# ESP32_with_USBC_SCH.net
KiCad netlist of a schematic drawn in Altium Designer
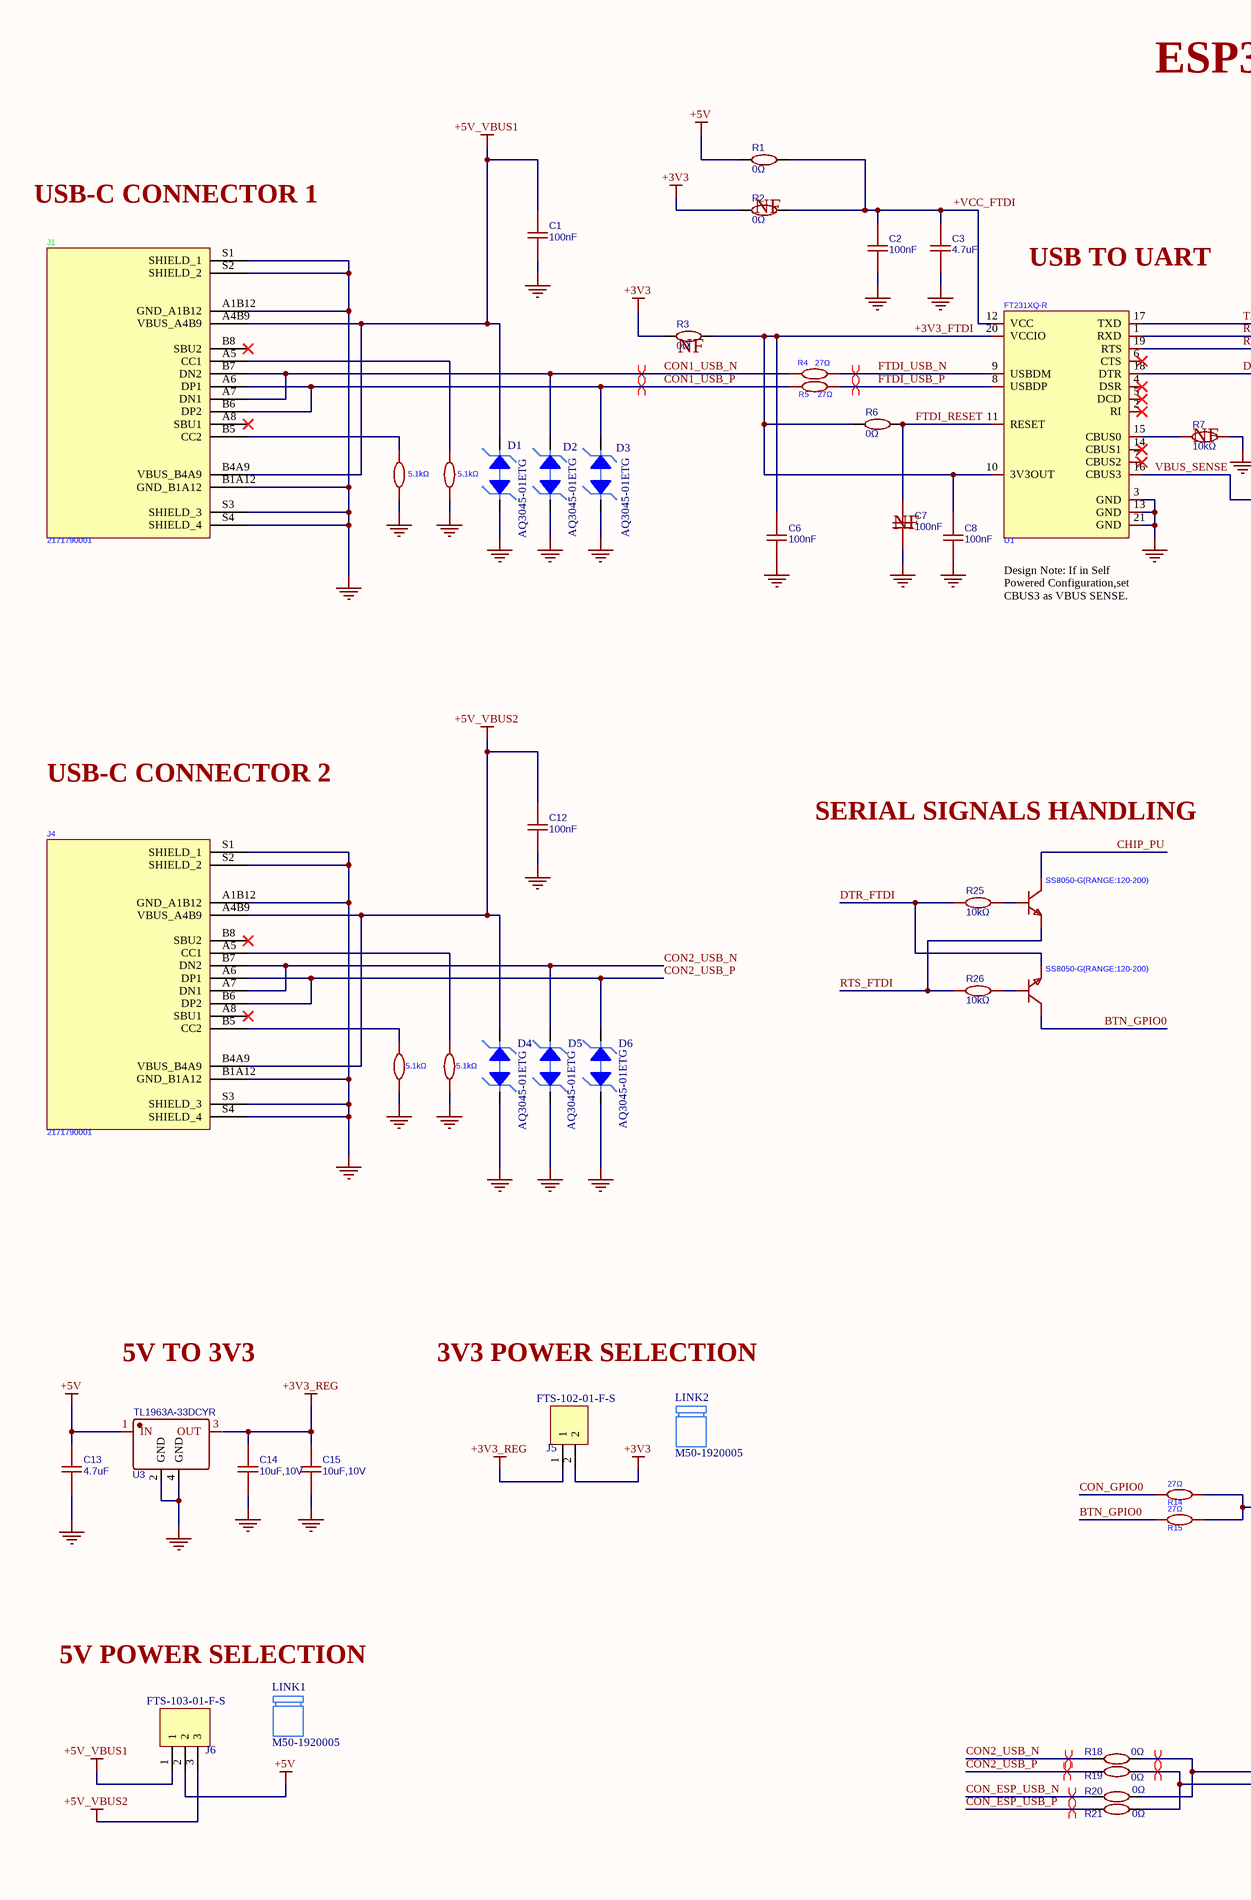
[diagram p0: ESP32 with USBC SCH.SchDoc, left]
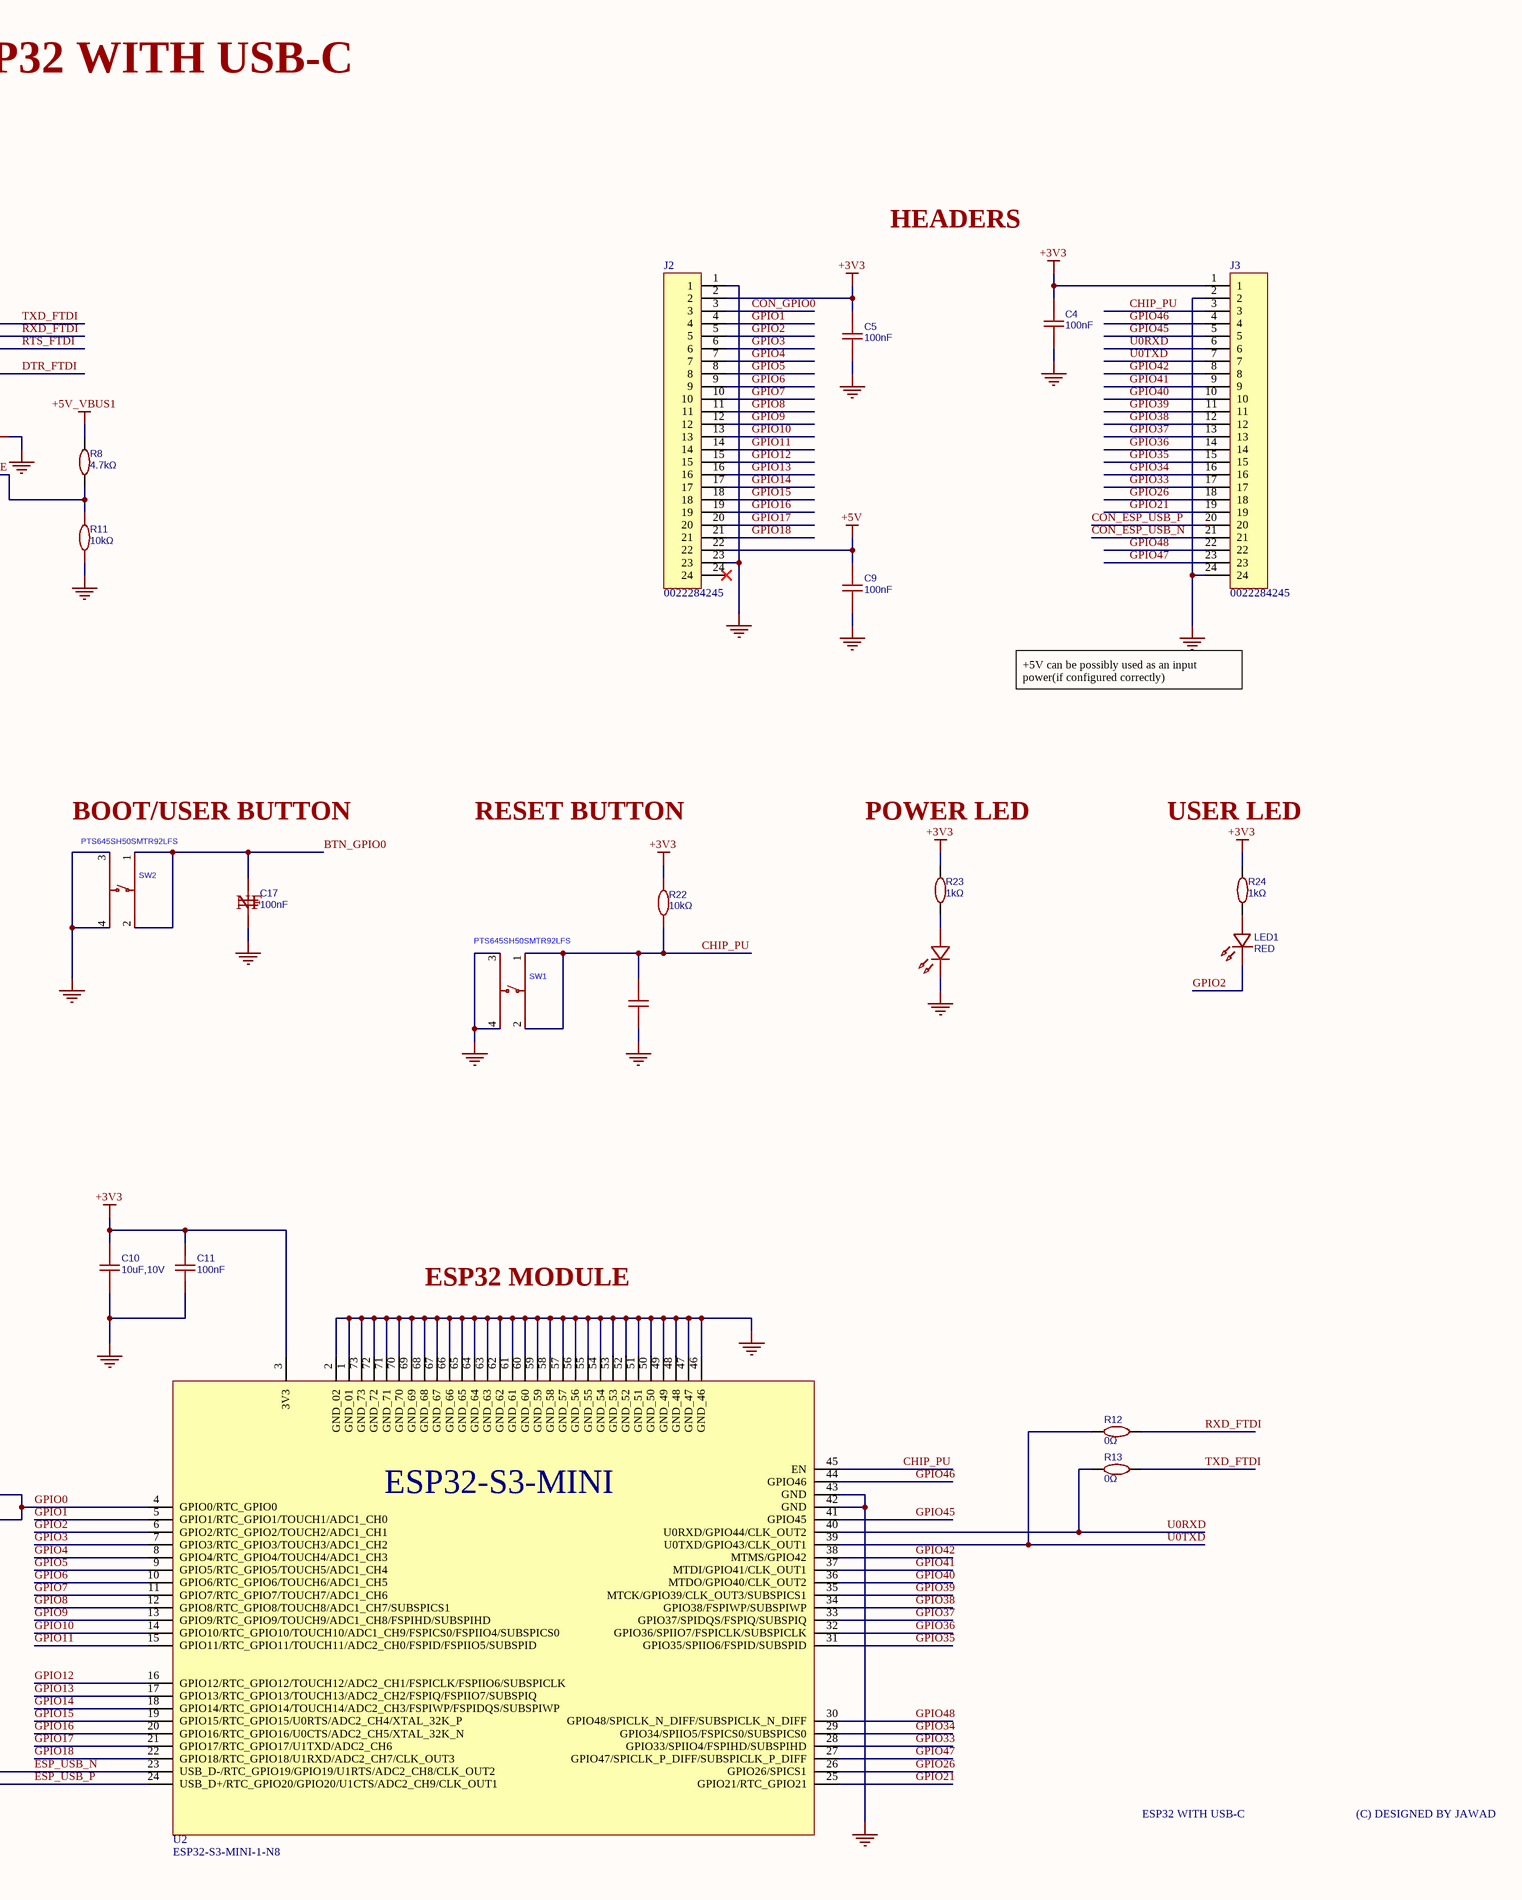
[diagram p1: ESP32 with USBC SCH.SchDoc, right]

(export (version "E")
  (design (tool "Eeschema 10.0.6"))
  (components
    (comp (ref "C1")
      (value "100nF")
      (footprint "C0402")
      (description "CAP CER 0.1UF 50V X7R 0402")
      (fields
        (field (name "MANUFACTURER") "SAMSUNG(三星)")
        (field (name "MANUFACTURER PART") "CL05B104KB5NNNC")
        (field (name "CONTRIBUTOR") "LCSC")
      )
      (libsource (lib "Schlib") (part "100nF,50V"))
    )
    (comp (ref "C2")
      (value "100nF")
      (footprint "C0402")
      (description "CAP CER 0.1UF 50V X7R 0402")
      (fields
        (field (name "MANUFACTURER") "SAMSUNG(三星)")
        (field (name "MANUFACTURER PART") "CL05B104KB5NNNC")
        (field (name "CONTRIBUTOR") "LCSC")
      )
      (libsource (lib "Schlib") (part "100nF,50V"))
    )
    (comp (ref "C3")
      (value "4.7uF")
      (footprint "C0402")
      (description "CAP CER 4.7UF 16V X5R 0402")
      (fields
        (field (name "MANUFACTURER") "SAMSUNG(三星)")
        (field (name "MANUFACTURER PART") "CL05A475MO5NUNC")
        (field (name "CONTRIBUTOR") "LCSC")
      )
      (libsource (lib "Schlib") (part "4.7uF"))
    )
    (comp (ref "C4")
      (value "100nF")
      (footprint "C0402")
      (description "CAP CER 0.1UF 50V X7R 0402")
      (fields
        (field (name "MANUFACTURER") "SAMSUNG(三星)")
        (field (name "MANUFACTURER PART") "CL05B104KB5NNNC")
        (field (name "CONTRIBUTOR") "LCSC")
      )
      (libsource (lib "Schlib") (part "100nF,50V"))
    )
    (comp (ref "C5")
      (value "100nF")
      (footprint "C0402")
      (description "CAP CER 0.1UF 50V X7R 0402")
      (fields
        (field (name "MANUFACTURER") "SAMSUNG(三星)")
        (field (name "MANUFACTURER PART") "CL05B104KB5NNNC")
        (field (name "CONTRIBUTOR") "LCSC")
      )
      (libsource (lib "Schlib") (part "100nF,50V"))
    )
    (comp (ref "C6")
      (value "100nF")
      (footprint "C0402")
      (description "CAP CER 0.1UF 50V X7R 0402")
      (fields
        (field (name "MANUFACTURER") "SAMSUNG(三星)")
        (field (name "MANUFACTURER PART") "CL05B104KB5NNNC")
        (field (name "CONTRIBUTOR") "LCSC")
      )
      (libsource (lib "Schlib") (part "100nF,50V"))
    )
    (comp (ref "C7")
      (value "100nF")
      (footprint "C0402")
      (description "CAP CER 0.1UF 50V X7R 0402")
      (fields
        (field (name "MANUFACTURER") "SAMSUNG(三星)")
        (field (name "MANUFACTURER PART") "CL05B104KB5NNNC")
        (field (name "CONTRIBUTOR") "LCSC")
      )
      (libsource (lib "Schlib") (part "100nF,50V"))
    )
    (comp (ref "C8")
      (value "100nF")
      (footprint "C0402")
      (description "CAP CER 0.1UF 50V X7R 0402")
      (fields
        (field (name "MANUFACTURER") "SAMSUNG(三星)")
        (field (name "MANUFACTURER PART") "CL05B104KB5NNNC")
        (field (name "CONTRIBUTOR") "LCSC")
      )
      (libsource (lib "Schlib") (part "100nF,50V"))
    )
    (comp (ref "C9")
      (value "100nF")
      (footprint "C0402")
      (description "CAP CER 0.1UF 50V X7R 0402")
      (fields
        (field (name "MANUFACTURER") "SAMSUNG(三星)")
        (field (name "MANUFACTURER PART") "CL05B104KB5NNNC")
        (field (name "CONTRIBUTOR") "LCSC")
      )
      (libsource (lib "Schlib") (part "100nF,50V"))
    )
    (comp (ref "C10")
      (value "10uF,10V")
      (footprint "C0402")
      (description "CAP CER 10UF 10V X5R 0402")
      (fields
        (field (name "MANUFACTURER") "muRata(村田)")
        (field (name "MANUFACTURER PART") "GRM155R61A106ME11D")
        (field (name "CONTRIBUTOR") "LCSC")
      )
      (libsource (lib "Schlib") (part "10uF"))
    )
    (comp (ref "C11")
      (value "100nF")
      (footprint "C0402")
      (description "CAP CER 0.1UF 50V X7R 0402")
      (fields
        (field (name "MANUFACTURER") "SAMSUNG(三星)")
        (field (name "MANUFACTURER PART") "CL05B104KB5NNNC")
        (field (name "CONTRIBUTOR") "LCSC")
      )
      (libsource (lib "Schlib") (part "100nF,50V"))
    )
    (comp (ref "C12")
      (value "100nF")
      (footprint "C0402")
      (description "CAP CER 0.1UF 50V X7R 0402")
      (fields
        (field (name "MANUFACTURER") "SAMSUNG(三星)")
        (field (name "MANUFACTURER PART") "CL05B104KB5NNNC")
        (field (name "CONTRIBUTOR") "LCSC")
      )
      (libsource (lib "Schlib") (part "100nF,50V"))
    )
    (comp (ref "C13")
      (value "4.7uF")
      (footprint "C0402")
      (description "CAP CER 4.7UF 16V X5R 0402")
      (fields
        (field (name "MANUFACTURER") "SAMSUNG(三星)")
        (field (name "MANUFACTURER PART") "CL05A475MO5NUNC")
        (field (name "CONTRIBUTOR") "LCSC")
      )
      (libsource (lib "Schlib") (part "4.7uF"))
    )
    (comp (ref "C14")
      (value "10uF,10V")
      (footprint "C0402")
      (description "CAP CER 10UF 10V X5R 0402")
      (fields
        (field (name "MANUFACTURER") "muRata(村田)")
        (field (name "MANUFACTURER PART") "GRM155R61A106ME11D")
        (field (name "CONTRIBUTOR") "LCSC")
      )
      (libsource (lib "Schlib") (part "10uF"))
    )
    (comp (ref "C15")
      (value "10uF,10V")
      (footprint "C0402")
      (description "CAP CER 10UF 10V X5R 0402")
      (fields
        (field (name "MANUFACTURER") "muRata(村田)")
        (field (name "MANUFACTURER PART") "GRM155R61A106ME11D")
        (field (name "CONTRIBUTOR") "LCSC")
      )
      (libsource (lib "Schlib") (part "10uF"))
    )
    (comp (ref "C16")
      (value "1uF,35V")
      (footprint "C0402")
      (description "CAP CER 1UF 35V X5R 0402")
      (fields
        (field (name "MANUFACTURER") "SAMSUNG(三星)")
        (field (name "MANUFACTURER PART") "CL05A105KL5NRNC")
      )
      (libsource (lib "Schlib") (part "CL05A105KL5NRNC"))
    )
    (comp (ref "C17")
      (value "100nF")
      (footprint "C0402")
      (description "CAP CER 0.1UF 50V X7R 0402")
      (fields
        (field (name "MANUFACTURER") "SAMSUNG(三星)")
        (field (name "MANUFACTURER PART") "CL05B104KB5NNNC")
        (field (name "CONTRIBUTOR") "LCSC")
      )
      (libsource (lib "Schlib") (part "100nF,50V"))
    )
    (comp (ref "D1")
      (value "AQ3045-01ETG")
      (footprint "SOD882")
      (description "TVS DIODE 5.3VWM 12VC SOD882")
      (fields (field (name "LCSC PART NUMBER") "C3710326"))
      (libsource (lib "Schlib") (part "AQ3045-01ETG"))
    )
    (comp (ref "D2")
      (value "AQ3045-01ETG")
      (footprint "SOD882")
      (description "TVS DIODE 5.3VWM 12VC SOD882")
      (fields (field (name "LCSC PART NUMBER") "C3710326"))
      (libsource (lib "Schlib") (part "AQ3045-01ETG"))
    )
    (comp (ref "D3")
      (value "AQ3045-01ETG")
      (footprint "SOD882")
      (description "TVS DIODE 5.3VWM 12VC SOD882")
      (fields (field (name "LCSC PART NUMBER") "C3710326"))
      (libsource (lib "Schlib") (part "AQ3045-01ETG"))
    )
    (comp (ref "D4")
      (value "AQ3045-01ETG")
      (footprint "SOD882")
      (description "TVS DIODE 5.3VWM 12VC SOD882")
      (fields (field (name "LCSC PART NUMBER") "C3710326"))
      (libsource (lib "Schlib") (part "AQ3045-01ETG"))
    )
    (comp (ref "D5")
      (value "AQ3045-01ETG")
      (footprint "SOD882")
      (description "TVS DIODE 5.3VWM 12VC SOD882")
      (fields (field (name "LCSC PART NUMBER") "C3710326"))
      (libsource (lib "Schlib") (part "AQ3045-01ETG"))
    )
    (comp (ref "D6")
      (value "AQ3045-01ETG")
      (footprint "SOD882")
      (description "TVS DIODE 5.3VWM 12VC SOD882")
      (fields (field (name "LCSC PART NUMBER") "C3710326"))
      (libsource (lib "Schlib") (part "AQ3045-01ETG"))
    )
    (comp (ref "J1")
      (value "2171790001")
      (footprint "USB-C-SMD_2171790001")
      (description "CONN RCP USB2.0 TYP C 24P SMD RA")
      (fields (field (name "MANUFACTURER") "MOLEX") (field (name "LCSC PART NUMBER") "C3197684"))
      (libsource (lib "Schlib") (part "2171790001"))
    )
    (comp (ref "J2")
      (value "0022284245")
      (footprint "HDR_1X24_2.54MM")
      (description "CONN HEADER VERT 24POS 2.54MM")
      (libsource (lib "") (part "0022284245_1"))
    )
    (comp (ref "J3")
      (value "0022284245")
      (footprint "HDR_1X24_2.54MM")
      (description "CONN HEADER VERT 24POS 2.54MM")
      (libsource (lib "Schlib") (part "0022284245"))
    )
    (comp (ref "J4")
      (value "2171790001")
      (footprint "USB-C-SMD_2171790001")
      (description "CONN RCP USB2.0 TYP C 24P SMD RA")
      (fields (field (name "MANUFACTURER") "MOLEX") (field (name "LCSC PART NUMBER") "C3197684"))
      (libsource (lib "Schlib") (part "2171790001"))
    )
    (comp (ref "J5")
      (value "FTS-102-01-F-S")
      (footprint "HDR_1X2_1.27MM")
      (description "CONN HEADER VERT 24POS 2.54MM")
      (fields (field (name "LCSC PART NUMBER") "C6045317"))
      (libsource (lib "Schlib") (part "FTS-102-01-F-S"))
    )
    (comp (ref "J6")
      (value "FTS-103-01-F-S")
      (footprint "HDR_1X3_1.27MM")
      (description "CONN HEADER VERT 3POS 1.27MM")
      (fields (field (name "LCSC PART NUMBER") "C3333578"))
      (libsource (lib "Schlib") (part "FTS-103-01-F-S"))
    )
    (comp (ref "LED1")
      (value "RED")
      (footprint "LED0402-RD_RED")
      (description "LED RED 0402 SMD")
      (fields
        (field (name "MANUFACTURER") "VISHAY(威世)")
        (field (name "MANUFACTURER PART") "VLMS1500-GS08")
        (field (name "CONTRIBUTOR") "LCSC")
      )
      (libsource (lib "Schlib") (part "VLMS1500-GS08"))
    )
    (comp (ref "LED2")
      (value "VLMG1500-GS08")
      (footprint "LED0402-RD_GREEN")
      (description "LED YLW-GRN 0402 SMD")
      (fields (field (name "MANUFACTURER") "VISHAY(威世)"))
      (libsource (lib "Schlib") (part "VLMG1500-GS08"))
    )
    (comp (ref "LINK1")
      (value "M50-1920005")
      (description "CONN SHUNT 1.27MM RED")
      (fields (field (name "LCSC PART NUMBER") "C6985646"))
      (libsource (lib "Schlib") (part "M50-1920005"))
    )
    (comp (ref "LINK2")
      (value "M50-1920005")
      (description "CONN SHUNT 1.27MM RED")
      (fields (field (name "LCSC PART NUMBER") "C6985646"))
      (libsource (lib "Schlib") (part "M50-1920005"))
    )
    (comp (ref "Q1")
      (value "SS8050-G(RANGE:120-200)")
      (footprint "SOT-23-3_L2.9-W1.3-P1.90-LS2.4-BR")
      (description "TRANS NPN 25V 1.5A SOT-23-3")
      (fields (field (name "MANUFACTURER") "CJ(江苏长电/长晶)") (field (name "LCSC PART NUMBER") "C164886"))
      (libsource (lib "Schlib") (part "SS8050-G(RANGE{colon}120-200)"))
    )
    (comp (ref "Q2")
      (value "SS8050-G(RANGE:120-200)")
      (footprint "SOT-23-3_L2.9-W1.3-P1.90-LS2.4-BR")
      (description "TRANS NPN 25V 1.5A SOT-23-3")
      (fields (field (name "MANUFACTURER") "CJ(江苏长电/长晶)") (field (name "LCSC PART NUMBER") "C164886"))
      (libsource (lib "Schlib") (part "SS8050-G(RANGE{colon}120-200)"))
    )
    (comp (ref "R1")
      (value "0Ω")
      (footprint "R0402")
      (description "RES 0 OHM JUMPER 1/16W 0402")
      (fields (field (name "MANUFACTURER") "YAGEO(国巨)") (field (name "MANUFACTURER PART") "RC0402FR-070RL"))
      (libsource (lib "Schlib") (part "0Ω"))
    )
    (comp (ref "R2")
      (value "0Ω")
      (footprint "R0402")
      (description "RES 0 OHM JUMPER 1/16W 0402")
      (fields (field (name "MANUFACTURER") "YAGEO(国巨)") (field (name "MANUFACTURER PART") "RC0402FR-070RL"))
      (libsource (lib "Schlib") (part "0Ω"))
    )
    (comp (ref "R3")
      (value "0Ω")
      (footprint "R0402")
      (description "RES 0 OHM JUMPER 1/16W 0402")
      (fields (field (name "MANUFACTURER") "YAGEO(国巨)") (field (name "MANUFACTURER PART") "RC0402FR-070RL"))
      (libsource (lib "Schlib") (part "0Ω"))
    )
    (comp (ref "R4")
      (value "27Ω")
      (footprint "R0402")
      (description "RES 27 OHM 1% 1/16W 0402")
      (fields (field (name "MANUFACTURER") "YAGEO(国巨)") (field (name "MANUFACTURER PART") "RC0402FR-0727RL"))
      (libsource (lib "Schlib") (part "RC0402FR-0727RL"))
    )
    (comp (ref "R5")
      (value "27Ω")
      (footprint "R0402")
      (description "RES 27 OHM 1% 1/16W 0402")
      (fields (field (name "MANUFACTURER") "YAGEO(国巨)") (field (name "MANUFACTURER PART") "RC0402FR-0727RL"))
      (libsource (lib "Schlib") (part "RC0402FR-0727RL"))
    )
    (comp (ref "R6")
      (value "0Ω")
      (footprint "R0402")
      (description "RES 0 OHM JUMPER 1/16W 0402")
      (fields (field (name "MANUFACTURER") "YAGEO(国巨)") (field (name "MANUFACTURER PART") "RC0402FR-070RL"))
      (libsource (lib "Schlib") (part "0Ω"))
    )
    (comp (ref "R7")
      (value "10kΩ")
      (footprint "R0402")
      (description "RES SMD 10K OHM 1% 1/16W 0402")
      (fields
        (field (name "MANUFACTURER") "YAGEO(国巨)")
        (field (name "MANUFACTURER PART") "AC0402FR-0710KL")
        (field (name "CONTRIBUTOR") "LCSC")
      )
      (libsource (lib "Schlib") (part "10kΩ"))
    )
    (comp (ref "R8")
      (value "4.7kΩ")
      (footprint "R0402")
      (description "RES 4.7K OHM 1% 1/16W 0402")
      (fields (field (name "MANUFACTURER") "YAGEO(国巨)") (field (name "MANUFACTURER PART") "RC0402FR-074K7L"))
      (libsource (lib "Schlib") (part "4.7kΩ"))
    )
    (comp (ref "R9")
      (value "5.1kΩ")
      (footprint "R0402")
      (description "RES SMD 5.1K OHM 1% 1/16W 0402")
      (fields (field (name "MANUFACTURER") "YAGEO(国巨)") (field (name "MANUFACTURER PART") "AC0402FR-075K1L"))
      (libsource (lib "Schlib") (part "AC0402FR-075K1L"))
    )
    (comp (ref "R10")
      (value "5.1kΩ")
      (footprint "R0402")
      (description "RES SMD 5.1K OHM 1% 1/16W 0402")
      (fields (field (name "MANUFACTURER") "YAGEO(国巨)") (field (name "MANUFACTURER PART") "AC0402FR-075K1L"))
      (libsource (lib "Schlib") (part "AC0402FR-075K1L"))
    )
    (comp (ref "R11")
      (value "10kΩ")
      (footprint "R0402")
      (description "RES SMD 10K OHM 1% 1/16W 0402")
      (fields
        (field (name "MANUFACTURER") "YAGEO(国巨)")
        (field (name "MANUFACTURER PART") "AC0402FR-0710KL")
        (field (name "CONTRIBUTOR") "LCSC")
      )
      (libsource (lib "Schlib") (part "10kΩ"))
    )
    (comp (ref "R12")
      (value "0Ω")
      (footprint "R0402")
      (description "RES 0 OHM JUMPER 1/16W 0402")
      (fields (field (name "MANUFACTURER") "YAGEO(国巨)") (field (name "MANUFACTURER PART") "RC0402FR-070RL"))
      (libsource (lib "Schlib") (part "0Ω"))
    )
    (comp (ref "R13")
      (value "0Ω")
      (footprint "R0402")
      (description "RES 0 OHM JUMPER 1/16W 0402")
      (fields (field (name "MANUFACTURER") "YAGEO(国巨)") (field (name "MANUFACTURER PART") "RC0402FR-070RL"))
      (libsource (lib "Schlib") (part "0Ω"))
    )
    (comp (ref "R14")
      (value "27Ω")
      (footprint "R0402")
      (description "RES 27 OHM 1% 1/16W 0402")
      (fields (field (name "MANUFACTURER") "YAGEO(国巨)") (field (name "MANUFACTURER PART") "RC0402FR-0727RL"))
      (libsource (lib "Schlib") (part "RC0402FR-0727RL"))
    )
    (comp (ref "R15")
      (value "27Ω")
      (footprint "R0402")
      (description "RES 27 OHM 1% 1/16W 0402")
      (fields (field (name "MANUFACTURER") "YAGEO(国巨)") (field (name "MANUFACTURER PART") "RC0402FR-0727RL"))
      (libsource (lib "Schlib") (part "RC0402FR-0727RL"))
    )
    (comp (ref "R16")
      (value "5.1kΩ")
      (footprint "R0402")
      (description "RES SMD 5.1K OHM 1% 1/16W 0402")
      (fields (field (name "MANUFACTURER") "YAGEO(国巨)") (field (name "MANUFACTURER PART") "AC0402FR-075K1L"))
      (libsource (lib "Schlib") (part "AC0402FR-075K1L"))
    )
    (comp (ref "R17")
      (value "5.1kΩ")
      (footprint "R0402")
      (description "RES SMD 5.1K OHM 1% 1/16W 0402")
      (fields (field (name "MANUFACTURER") "YAGEO(国巨)") (field (name "MANUFACTURER PART") "AC0402FR-075K1L"))
      (libsource (lib "Schlib") (part "AC0402FR-075K1L"))
    )
    (comp (ref "R18")
      (value "0Ω")
      (footprint "R0402")
      (description "RES 0 OHM JUMPER 1/16W 0402")
      (fields (field (name "MANUFACTURER") "YAGEO(国巨)") (field (name "MANUFACTURER PART") "RC0402FR-070RL"))
      (libsource (lib "Schlib") (part "0Ω"))
    )
    (comp (ref "R19")
      (value "0Ω")
      (footprint "R0402")
      (description "RES 0 OHM JUMPER 1/16W 0402")
      (fields (field (name "MANUFACTURER") "YAGEO(国巨)") (field (name "MANUFACTURER PART") "RC0402FR-070RL"))
      (libsource (lib "Schlib") (part "0Ω"))
    )
    (comp (ref "R20")
      (value "0Ω")
      (footprint "R0402")
      (description "RES 0 OHM JUMPER 1/16W 0402")
      (fields (field (name "MANUFACTURER") "YAGEO(国巨)") (field (name "MANUFACTURER PART") "RC0402FR-070RL"))
      (libsource (lib "Schlib") (part "0Ω"))
    )
    (comp (ref "R21")
      (value "0Ω")
      (footprint "R0402")
      (description "RES 0 OHM JUMPER 1/16W 0402")
      (fields (field (name "MANUFACTURER") "YAGEO(国巨)") (field (name "MANUFACTURER PART") "RC0402FR-070RL"))
      (libsource (lib "Schlib") (part "0Ω"))
    )
    (comp (ref "R22")
      (value "10kΩ")
      (footprint "R0402")
      (description "RES SMD 10K OHM 1% 1/16W 0402")
      (fields
        (field (name "MANUFACTURER") "YAGEO(国巨)")
        (field (name "MANUFACTURER PART") "AC0402FR-0710KL")
        (field (name "CONTRIBUTOR") "LCSC")
      )
      (libsource (lib "Schlib") (part "10kΩ"))
    )
    (comp (ref "R23")
      (value "1kΩ")
      (footprint "R0402")
      (description "RES 1K OHM 1% 1/16W 0402")
      (fields (field (name "MANUFACTURER") "YAGEO(国巨)") (field (name "MANUFACTURER PART") "RC0402FR-071KL"))
      (libsource (lib "Schlib") (part "1kΩ"))
    )
    (comp (ref "R24")
      (value "1kΩ")
      (footprint "R0402")
      (description "RES 1K OHM 1% 1/16W 0402")
      (fields (field (name "MANUFACTURER") "YAGEO(国巨)") (field (name "MANUFACTURER PART") "RC0402FR-071KL"))
      (libsource (lib "Schlib") (part "1kΩ"))
    )
    (comp (ref "R25")
      (value "10kΩ")
      (footprint "R0402")
      (description "RES SMD 10K OHM 1% 1/16W 0402")
      (fields
        (field (name "MANUFACTURER") "YAGEO(国巨)")
        (field (name "MANUFACTURER PART") "AC0402FR-0710KL")
        (field (name "CONTRIBUTOR") "LCSC")
      )
      (libsource (lib "Schlib") (part "10kΩ"))
    )
    (comp (ref "R26")
      (value "10kΩ")
      (footprint "R0402")
      (description "RES SMD 10K OHM 1% 1/16W 0402")
      (fields
        (field (name "MANUFACTURER") "YAGEO(国巨)")
        (field (name "MANUFACTURER PART") "AC0402FR-0710KL")
        (field (name "CONTRIBUTOR") "LCSC")
      )
      (libsource (lib "Schlib") (part "10kΩ"))
    )
    (comp (ref "SW1")
      (value "PTS645SH50SMTR92LFS")
      (footprint "KEY-SMD_4P-L6.0-W6.0-P4.50-LS9.0")
      (description "Tactile Switch SPST-NO Top Actuated Surface Mount")
      (fields (field (name "MANUFACTURER") "C&K") (field (name "LCSC PART NUMBER") "C221869"))
      (libsource (lib "Schlib") (part "PTS645SH50SMTR92LFS"))
    )
    (comp (ref "SW2")
      (value "PTS645SH50SMTR92LFS")
      (footprint "KEY-SMD_4P-L6.0-W6.0-P4.50-LS9.0")
      (description "Tactile Switch SPST-NO Top Actuated Surface Mount")
      (fields (field (name "MANUFACTURER") "C&K") (field (name "LCSC PART NUMBER") "C221869"))
      (libsource (lib "Schlib") (part "PTS645SH50SMTR92LFS"))
    )
    (comp (ref "U1")
      (value "FT231XQ-R")
      (footprint "QFN-20_L4.0-W4.0-P0.50-BL-EP2.2")
      (description "IC USB SERIAL FULL UART 20QFN")
      (fields (field (name "MANUFACTURER") "FTDI(飞特帝亚)") (field (name "LCSC PART NUMBER") "C132159"))
      (libsource (lib "Schlib") (part "FT231XQ-R"))
    )
    (comp (ref "U2")
      (value "ESP32-S3-MINI-1-N8")
      (footprint "XCVR_ESP32-S3-MINI-1-N8")
      (fields (field (name "LCSC PART NUMBER") "C2913206"))
      (libsource (lib "Schlib") (part "ESP32-S3-MINI-1-N8"))
    )
    (comp (ref "U3")
      (value "TL1963A-33DCYR")
      (footprint "SOT-223_L6.5-W3.5-P2.30-LS7.0-BR")
      (description "IC REG LIN 3.3V 1.5A SOT-223-4")
      (fields
        (field (name "MANUFACTURER") "TI(德州仪器)")
        (field (name "LCSC PART NUMBER") "C181262")
        (field (name "CONTRIBUTOR") "LCSC")
      )
      (libsource (lib "Schlib") (part "TL1963A-33DCYR"))
    )
  )
  (nets
    (net (code "1") (name "+3V3") (class "Default")
      (node (ref "C10") (pin "2") (pinfunction "2_2") (pintype "passive"))
      (node (ref "C11") (pin "2") (pinfunction "2_2") (pintype "passive"))
      (node (ref "C4") (pin "2") (pinfunction "2_2") (pintype "passive"))
      (node (ref "C5") (pin "2") (pinfunction "2_2") (pintype "passive"))
      (node (ref "J2") (pin "2") (pinfunction "2_2") (pintype "passive"))
      (node (ref "J3") (pin "1") (pinfunction "1_1") (pintype "passive"))
      (node (ref "J5") (pin "2") (pinfunction "2_2") (pintype "passive"))
      (node (ref "R2") (pin "1") (pinfunction "1_1") (pintype "passive"))
      (node (ref "R22") (pin "2") (pinfunction "2_2") (pintype "passive"))
      (node (ref "R23") (pin "2") (pinfunction "2_2") (pintype "passive"))
      (node (ref "R24") (pin "2") (pinfunction "2_2") (pintype "passive"))
      (node (ref "R3") (pin "1") (pinfunction "1_1") (pintype "passive"))
      (node (ref "U2") (pin "3") (pinfunction "3V3_3") (pintype "passive"))
    )
    (net (code "2") (name "+3V3_REG") (class "Default")
      (node (ref "C14") (pin "2") (pinfunction "2_2") (pintype "passive"))
      (node (ref "C15") (pin "2") (pinfunction "2_2") (pintype "passive"))
      (node (ref "J5") (pin "1") (pinfunction "1_1") (pintype "passive"))
    )
    (net (code "3") (name "+5V") (class "Default")
      (node (ref "C13") (pin "2") (pinfunction "2_2") (pintype "passive"))
      (node (ref "C9") (pin "2") (pinfunction "2_2") (pintype "passive"))
      (node (ref "J2") (pin "22") (pinfunction "22_22") (pintype "passive"))
      (node (ref "J6") (pin "2") (pinfunction "2_2") (pintype "passive"))
      (node (ref "R1") (pin "1") (pinfunction "1_1") (pintype "passive"))
      (node (ref "U3") (pin "1") (pinfunction "IN_1") (pintype "passive"))
    )
    (net (code "4") (name "+5V_VBUS1") (class "Default")
      (node (ref "C1") (pin "2") (pinfunction "2_2") (pintype "passive"))
      (node (ref "D1") (pin "1") (pinfunction "1_1") (pintype "passive"))
      (node (ref "J1") (pin "A4B9") (pinfunction "VBUS_A4B9_A4B9") (pintype "passive"))
      (node (ref "J1") (pin "B4A9") (pinfunction "VBUS_B4A9_B4A9") (pintype "passive"))
      (node (ref "J6") (pin "1") (pinfunction "1_1") (pintype "passive"))
      (node (ref "R8") (pin "2") (pinfunction "2_2") (pintype "passive"))
    )
    (net (code "5") (name "+5V_VBUS2") (class "Default")
      (node (ref "C12") (pin "2") (pinfunction "2_2") (pintype "passive"))
      (node (ref "D4") (pin "1") (pinfunction "1_1") (pintype "passive"))
      (node (ref "J4") (pin "A4B9") (pinfunction "VBUS_A4B9_A4B9") (pintype "passive"))
      (node (ref "J4") (pin "B4A9") (pinfunction "VBUS_B4A9_B4A9") (pintype "passive"))
      (node (ref "J6") (pin "3") (pinfunction "3_3") (pintype "passive"))
    )
    (net (code "6") (name "/+3V3_FTDI") (class "Default")
      (node (ref "C6") (pin "2") (pinfunction "2_2") (pintype "passive"))
      (node (ref "C8") (pin "2") (pinfunction "2_2") (pintype "passive"))
      (node (ref "R3") (pin "2") (pinfunction "2_2") (pintype "passive"))
      (node (ref "R6") (pin "1") (pinfunction "1_1") (pintype "passive"))
      (node (ref "U1") (pin "10") (pinfunction "3V3OUT_10") (pintype "passive"))
      (node (ref "U1") (pin "20") (pinfunction "VCCIO_20") (pintype "passive"))
    )
    (net (code "7") (name "/+VCC_FTDI") (class "Default")
      (node (ref "C2") (pin "2") (pinfunction "2_2") (pintype "passive"))
      (node (ref "C3") (pin "2") (pinfunction "2_2") (pintype "passive"))
      (node (ref "R1") (pin "2") (pinfunction "2_2") (pintype "passive"))
      (node (ref "R2") (pin "2") (pinfunction "2_2") (pintype "passive"))
      (node (ref "U1") (pin "12") (pinfunction "VCC_12") (pintype "passive"))
    )
    (net (code "8") (name "/BTN_GPIO0") (class "Default")
      (node (ref "C17") (pin "2") (pinfunction "2_2") (pintype "passive"))
      (node (ref "Q2") (pin "3") (pinfunction "C_3") (pintype "passive"))
      (node (ref "R15") (pin "1") (pinfunction "1_1") (pintype "passive"))
      (node (ref "SW2") (pin "1") (pinfunction "1_1") (pintype "passive"))
      (node (ref "SW2") (pin "2") (pinfunction "2_2") (pintype "passive"))
    )
    (net (code "9") (name "/CHIP_PU") (class "Default")
      (node (ref "C16") (pin "2") (pinfunction "2_2") (pintype "passive"))
      (node (ref "J3") (pin "3") (pinfunction "3_3") (pintype "passive"))
      (node (ref "Q1") (pin "3") (pinfunction "C_3") (pintype "passive"))
      (node (ref "R22") (pin "1") (pinfunction "1_1") (pintype "passive"))
      (node (ref "SW1") (pin "1") (pinfunction "1_1") (pintype "passive"))
      (node (ref "SW1") (pin "2") (pinfunction "2_2") (pintype "passive"))
      (node (ref "U2") (pin "45") (pinfunction "EN_45") (pintype "passive"))
    )
    (net (code "10") (name "/CON1_USB_N") (class "Default")
      (node (ref "D2") (pin "1") (pinfunction "1_1") (pintype "passive"))
      (node (ref "J1") (pin "A7") (pinfunction "DN1_A7") (pintype "passive"))
      (node (ref "J1") (pin "B7") (pinfunction "DN2_B7") (pintype "passive"))
      (node (ref "R4") (pin "1") (pinfunction "1_1") (pintype "passive"))
    )
    (net (code "11") (name "/CON1_USB_P") (class "Default")
      (node (ref "D3") (pin "1") (pinfunction "1_1") (pintype "passive"))
      (node (ref "J1") (pin "A6") (pinfunction "DP1_A6") (pintype "passive"))
      (node (ref "J1") (pin "B6") (pinfunction "DP2_B6") (pintype "passive"))
      (node (ref "R5") (pin "1") (pinfunction "1_1") (pintype "passive"))
    )
    (net (code "12") (name "/CON2_USB_N") (class "Default")
      (node (ref "D5") (pin "1") (pinfunction "1_1") (pintype "passive"))
      (node (ref "J4") (pin "A7") (pinfunction "DN1_A7") (pintype "passive"))
      (node (ref "J4") (pin "B7") (pinfunction "DN2_B7") (pintype "passive"))
      (node (ref "R18") (pin "1") (pinfunction "1_1") (pintype "passive"))
    )
    (net (code "13") (name "/CON2_USB_P") (class "Default")
      (node (ref "D6") (pin "1") (pinfunction "1_1") (pintype "passive"))
      (node (ref "J4") (pin "A6") (pinfunction "DP1_A6") (pintype "passive"))
      (node (ref "J4") (pin "B6") (pinfunction "DP2_B6") (pintype "passive"))
      (node (ref "R19") (pin "1") (pinfunction "1_1") (pintype "passive"))
    )
    (net (code "14") (name "/CON_ESP_USB_N") (class "Default")
      (node (ref "J3") (pin "21") (pinfunction "21_21") (pintype "passive"))
      (node (ref "R20") (pin "1") (pinfunction "1_1") (pintype "passive"))
    )
    (net (code "15") (name "/CON_ESP_USB_P") (class "Default")
      (node (ref "J3") (pin "20") (pinfunction "20_20") (pintype "passive"))
      (node (ref "R21") (pin "1") (pinfunction "1_1") (pintype "passive"))
    )
    (net (code "16") (name "/CON_GPIO0") (class "Default")
      (node (ref "J2") (pin "3") (pinfunction "3_3") (pintype "passive"))
      (node (ref "R14") (pin "1") (pinfunction "1_1") (pintype "passive"))
    )
    (net (code "17") (name "/DTR_FTDI") (class "Default")
      (node (ref "Q2") (pin "2") (pinfunction "E_2") (pintype "passive"))
      (node (ref "R25") (pin "2") (pinfunction "2_2") (pintype "passive"))
      (node (ref "U1") (pin "18") (pinfunction "DTR_18") (pintype "passive"))
    )
    (net (code "18") (name "/ESP_USB_N") (class "Default")
      (node (ref "R18") (pin "2") (pinfunction "2_2") (pintype "passive"))
      (node (ref "R20") (pin "2") (pinfunction "2_2") (pintype "passive"))
      (node (ref "U2") (pin "23") (pinfunction "USB_D-/RTC_GPIO19/GPIO19/U1RTS/ADC2_CH8/CLK_OUT2_23") (pintype "passive"))
    )
    (net (code "19") (name "/ESP_USB_P") (class "Default")
      (node (ref "R19") (pin "2") (pinfunction "2_2") (pintype "passive"))
      (node (ref "R21") (pin "2") (pinfunction "2_2") (pintype "passive"))
      (node (ref "U2") (pin "24") (pinfunction "USB_D+/RTC_GPIO20/GPIO20/U1CTS/ADC2_CH9/CLK_OUT1_24") (pintype "passive"))
    )
    (net (code "20") (name "/FTDI_RESET") (class "Default")
      (node (ref "C7") (pin "2") (pinfunction "2_2") (pintype "passive"))
      (node (ref "R6") (pin "2") (pinfunction "2_2") (pintype "passive"))
      (node (ref "U1") (pin "11") (pinfunction "RESET_11") (pintype "passive"))
    )
    (net (code "21") (name "/FTDI_USB_N") (class "Default")
      (node (ref "R4") (pin "2") (pinfunction "2_2") (pintype "passive"))
      (node (ref "U1") (pin "9") (pinfunction "USBDM_9") (pintype "passive"))
    )
    (net (code "22") (name "/FTDI_USB_P") (class "Default")
      (node (ref "R5") (pin "2") (pinfunction "2_2") (pintype "passive"))
      (node (ref "U1") (pin "8") (pinfunction "USBDP_8") (pintype "passive"))
    )
    (net (code "23") (name "/GPIO0") (class "Default")
      (node (ref "R14") (pin "2") (pinfunction "2_2") (pintype "passive"))
      (node (ref "R15") (pin "2") (pinfunction "2_2") (pintype "passive"))
      (node (ref "U2") (pin "4") (pinfunction "GPIO0/RTC_GPIO0_4") (pintype "passive"))
    )
    (net (code "24") (name "/GPIO1") (class "Default")
      (node (ref "J2") (pin "4") (pinfunction "4_4") (pintype "passive"))
      (node (ref "U2") (pin "5") (pinfunction "GPIO1/RTC_GPIO1/TOUCH1/ADC1_CH0_5") (pintype "passive"))
    )
    (net (code "25") (name "/GPIO2") (class "Default")
      (node (ref "J2") (pin "5") (pinfunction "5_5") (pintype "passive"))
      (node (ref "LED1") (pin "1") (pinfunction "-_1") (pintype "passive"))
      (node (ref "U2") (pin "6") (pinfunction "GPIO2/RTC_GPIO2/TOUCH2/ADC1_CH1_6") (pintype "passive"))
    )
    (net (code "26") (name "/GPIO3") (class "Default")
      (node (ref "J2") (pin "6") (pinfunction "6_6") (pintype "passive"))
      (node (ref "U2") (pin "7") (pinfunction "GPIO3/RTC_GPIO3/TOUCH3/ADC1_CH2_7") (pintype "passive"))
    )
    (net (code "27") (name "/GPIO4") (class "Default")
      (node (ref "J2") (pin "7") (pinfunction "7_7") (pintype "passive"))
      (node (ref "U2") (pin "8") (pinfunction "GPIO4/RTC_GPIO4/TOUCH4/ADC1_CH3_8") (pintype "passive"))
    )
    (net (code "28") (name "/GPIO5") (class "Default")
      (node (ref "J2") (pin "8") (pinfunction "8_8") (pintype "passive"))
      (node (ref "U2") (pin "9") (pinfunction "GPIO5/RTC_GPIO5/TOUCH5/ADC1_CH4_9") (pintype "passive"))
    )
    (net (code "29") (name "/GPIO6") (class "Default")
      (node (ref "J2") (pin "9") (pinfunction "9_9") (pintype "passive"))
      (node (ref "U2") (pin "10") (pinfunction "GPIO6/RTC_GPIO6/TOUCH6/ADC1_CH5_10") (pintype "passive"))
    )
    (net (code "30") (name "/GPIO7") (class "Default")
      (node (ref "J2") (pin "10") (pinfunction "10_10") (pintype "passive"))
      (node (ref "U2") (pin "11") (pinfunction "GPIO7/RTC_GPIO7/TOUCH7/ADC1_CH6_11") (pintype "passive"))
    )
    (net (code "31") (name "/GPIO8") (class "Default")
      (node (ref "J2") (pin "11") (pinfunction "11_11") (pintype "passive"))
      (node (ref "U2") (pin "12") (pinfunction "GPIO8/RTC_GPIO8/TOUCH8/ADC1_CH7/SUBSPICS1_12") (pintype "passive"))
    )
    (net (code "32") (name "/GPIO9") (class "Default")
      (node (ref "J2") (pin "12") (pinfunction "12_12") (pintype "passive"))
      (node (ref "U2") (pin "13") (pinfunction "GPIO9/RTC_GPIO9/TOUCH9/ADC1_CH8/FSPIHD/SUBSPIHD_13") (pintype "passive"))
    )
    (net (code "33") (name "/GPIO10") (class "Default")
      (node (ref "J2") (pin "13") (pinfunction "13_13") (pintype "passive"))
      (node (ref "U2") (pin "14") (pinfunction "GPIO10/RTC_GPIO10/TOUCH10/ADC1_CH9/FSPICS0/FSPIIO4/SUBSPICS0_14") (pintype "passive"))
    )
    (net (code "34") (name "/GPIO11") (class "Default")
      (node (ref "J2") (pin "14") (pinfunction "14_14") (pintype "passive"))
      (node (ref "U2") (pin "15") (pinfunction "GPIO11/RTC_GPIO11/TOUCH11/ADC2_CH0/FSPID/FSPIIO5/SUBSPID_15") (pintype "passive"))
    )
    (net (code "35") (name "/GPIO12") (class "Default")
      (node (ref "J2") (pin "15") (pinfunction "15_15") (pintype "passive"))
      (node (ref "U2") (pin "16") (pinfunction "GPIO12/RTC_GPIO12/TOUCH12/ADC2_CH1/FSPICLK/FSPIIO6/SUBSPICLK_16") (pintype "passive"))
    )
    (net (code "36") (name "/GPIO13") (class "Default")
      (node (ref "J2") (pin "16") (pinfunction "16_16") (pintype "passive"))
      (node (ref "U2") (pin "17") (pinfunction "GPIO13/RTC_GPIO13/TOUCH13/ADC2_CH2/FSPIQ/FSPIIO7/SUBSPIQ_17") (pintype "passive"))
    )
    (net (code "37") (name "/GPIO14") (class "Default")
      (node (ref "J2") (pin "17") (pinfunction "17_17") (pintype "passive"))
      (node (ref "U2") (pin "18") (pinfunction "GPIO14/RTC_GPIO14/TOUCH14/ADC2_CH3/FSPIWP/FSPIDQS/SUBSPIWP_18") (pintype "passive"))
    )
    (net (code "38") (name "/GPIO15") (class "Default")
      (node (ref "J2") (pin "18") (pinfunction "18_18") (pintype "passive"))
      (node (ref "U2") (pin "19") (pinfunction "GPIO15/RTC_GPIO15/U0RTS/ADC2_CH4/XTAL_32K_P_19") (pintype "passive"))
    )
    (net (code "39") (name "/GPIO16") (class "Default")
      (node (ref "J2") (pin "19") (pinfunction "19_19") (pintype "passive"))
      (node (ref "U2") (pin "20") (pinfunction "GPIO16/RTC_GPIO16/U0CTS/ADC2_CH5/XTAL_32K_N_20") (pintype "passive"))
    )
    (net (code "40") (name "/GPIO17") (class "Default")
      (node (ref "J2") (pin "20") (pinfunction "20_20") (pintype "passive"))
      (node (ref "U2") (pin "21") (pinfunction "GPIO17/RTC_GPIO17/U1TXD/ADC2_CH6_21") (pintype "passive"))
    )
    (net (code "41") (name "/GPIO18") (class "Default")
      (node (ref "J2") (pin "21") (pinfunction "21_21") (pintype "passive"))
      (node (ref "U2") (pin "22") (pinfunction "GPIO18/RTC_GPIO18/U1RXD/ADC2_CH7/CLK_OUT3_22") (pintype "passive"))
    )
    (net (code "42") (name "/GPIO21") (class "Default")
      (node (ref "J3") (pin "19") (pinfunction "19_19") (pintype "passive"))
      (node (ref "U2") (pin "25") (pinfunction "GPIO21/RTC_GPIO21_25") (pintype "passive"))
    )
    (net (code "43") (name "/GPIO26") (class "Default")
      (node (ref "J3") (pin "18") (pinfunction "18_18") (pintype "passive"))
      (node (ref "U2") (pin "26") (pinfunction "GPIO26/SPICS1_26") (pintype "passive"))
    )
    (net (code "44") (name "/GPIO33") (class "Default")
      (node (ref "J3") (pin "17") (pinfunction "17_17") (pintype "passive"))
      (node (ref "U2") (pin "28") (pinfunction "GPIO33/SPIIO4/FSPIHD/SUBSPIHD_28") (pintype "passive"))
    )
    (net (code "45") (name "/GPIO34") (class "Default")
      (node (ref "J3") (pin "16") (pinfunction "16_16") (pintype "passive"))
      (node (ref "U2") (pin "29") (pinfunction "GPIO34/SPIIO5/FSPICS0/SUBSPICS0_29") (pintype "passive"))
    )
    (net (code "46") (name "/GPIO35") (class "Default")
      (node (ref "J3") (pin "15") (pinfunction "15_15") (pintype "passive"))
      (node (ref "U2") (pin "31") (pinfunction "GPIO35/SPIIO6/FSPID/SUBSPID_31") (pintype "passive"))
    )
    (net (code "47") (name "/GPIO36") (class "Default")
      (node (ref "J3") (pin "14") (pinfunction "14_14") (pintype "passive"))
      (node (ref "U2") (pin "32") (pinfunction "GPIO36/SPIIO7/FSPICLK/SUBSPICLK_32") (pintype "passive"))
    )
    (net (code "48") (name "/GPIO37") (class "Default")
      (node (ref "J3") (pin "13") (pinfunction "13_13") (pintype "passive"))
      (node (ref "U2") (pin "33") (pinfunction "GPIO37/SPIDQS/FSPIQ/SUBSPIQ_33") (pintype "passive"))
    )
    (net (code "49") (name "/GPIO38") (class "Default")
      (node (ref "J3") (pin "12") (pinfunction "12_12") (pintype "passive"))
      (node (ref "U2") (pin "34") (pinfunction "GPIO38/FSPIWP/SUBSPIWP_34") (pintype "passive"))
    )
    (net (code "50") (name "/GPIO39") (class "Default")
      (node (ref "J3") (pin "11") (pinfunction "11_11") (pintype "passive"))
      (node (ref "U2") (pin "35") (pinfunction "MTCK/GPIO39/CLK_OUT3/SUBSPICS1_35") (pintype "passive"))
    )
    (net (code "51") (name "/GPIO40") (class "Default")
      (node (ref "J3") (pin "10") (pinfunction "10_10") (pintype "passive"))
      (node (ref "U2") (pin "36") (pinfunction "MTDO/GPIO40/CLK_OUT2_36") (pintype "passive"))
    )
    (net (code "52") (name "/GPIO41") (class "Default")
      (node (ref "J3") (pin "9") (pinfunction "9_9") (pintype "passive"))
      (node (ref "U2") (pin "37") (pinfunction "MTDI/GPIO41/CLK_OUT1_37") (pintype "passive"))
    )
    (net (code "53") (name "/GPIO42") (class "Default")
      (node (ref "J3") (pin "8") (pinfunction "8_8") (pintype "passive"))
      (node (ref "U2") (pin "38") (pinfunction "MTMS/GPIO42_38") (pintype "passive"))
    )
    (net (code "54") (name "/GPIO45") (class "Default")
      (node (ref "J3") (pin "5") (pinfunction "5_5") (pintype "passive"))
      (node (ref "U2") (pin "41") (pinfunction "GPIO45_41") (pintype "passive"))
    )
    (net (code "55") (name "/GPIO46") (class "Default")
      (node (ref "J3") (pin "4") (pinfunction "4_4") (pintype "passive"))
      (node (ref "U2") (pin "44") (pinfunction "GPIO46_44") (pintype "passive"))
    )
    (net (code "56") (name "/GPIO47") (class "Default")
      (node (ref "J3") (pin "23") (pinfunction "23_23") (pintype "passive"))
      (node (ref "U2") (pin "27") (pinfunction "GPIO47/SPICLK_P_DIFF/SUBSPICLK_P_DIFF_27") (pintype "passive"))
    )
    (net (code "57") (name "/GPIO48") (class "Default")
      (node (ref "J3") (pin "22") (pinfunction "22_22") (pintype "passive"))
      (node (ref "U2") (pin "30") (pinfunction "GPIO48/SPICLK_N_DIFF/SUBSPICLK_N_DIFF_30") (pintype "passive"))
    )
    (net (code "58") (name "/RTS_FTDI") (class "Default")
      (node (ref "Q1") (pin "2") (pinfunction "E_2") (pintype "passive"))
      (node (ref "R26") (pin "2") (pinfunction "2_2") (pintype "passive"))
      (node (ref "U1") (pin "19") (pinfunction "RTS_19") (pintype "passive"))
    )
    (net (code "59") (name "/RXD_FTDI") (class "Default")
      (node (ref "R12") (pin "2") (pinfunction "2_2") (pintype "passive"))
      (node (ref "U1") (pin "1") (pinfunction "RXD_1") (pintype "passive"))
    )
    (net (code "60") (name "/TXD_FTDI") (class "Default")
      (node (ref "R13") (pin "2") (pinfunction "2_2") (pintype "passive"))
      (node (ref "U1") (pin "17") (pinfunction "TXD_17") (pintype "passive"))
    )
    (net (code "61") (name "/U0RXD") (class "Default")
      (node (ref "J3") (pin "6") (pinfunction "6_6") (pintype "passive"))
      (node (ref "R13") (pin "1") (pinfunction "1_1") (pintype "passive"))
      (node (ref "U2") (pin "40") (pinfunction "U0RXD/GPIO44/CLK_OUT2_40") (pintype "passive"))
    )
    (net (code "62") (name "/U0TXD") (class "Default")
      (node (ref "J3") (pin "7") (pinfunction "7_7") (pintype "passive"))
      (node (ref "R12") (pin "1") (pinfunction "1_1") (pintype "passive"))
      (node (ref "U2") (pin "39") (pinfunction "U0TXD/GPIO43/CLK_OUT1_39") (pintype "passive"))
    )
    (net (code "63") (name "/VBUS_SENSE") (class "Default")
      (node (ref "R11") (pin "2") (pinfunction "2_2") (pintype "passive"))
      (node (ref "R8") (pin "1") (pinfunction "1_1") (pintype "passive"))
      (node (ref "U1") (pin "16") (pinfunction "CBUS3_16") (pintype "passive"))
    )
    (net (code "64") (name "GND") (class "Default")
      (node (ref "C1") (pin "1") (pinfunction "1_1") (pintype "passive"))
      (node (ref "C10") (pin "1") (pinfunction "1_1") (pintype "passive"))
      (node (ref "C11") (pin "1") (pinfunction "1_1") (pintype "passive"))
      (node (ref "C12") (pin "1") (pinfunction "1_1") (pintype "passive"))
      (node (ref "C13") (pin "1") (pinfunction "1_1") (pintype "passive"))
      (node (ref "C14") (pin "1") (pinfunction "1_1") (pintype "passive"))
      (node (ref "C15") (pin "1") (pinfunction "1_1") (pintype "passive"))
      (node (ref "C16") (pin "1") (pinfunction "1_1") (pintype "passive"))
      (node (ref "C17") (pin "1") (pinfunction "1_1") (pintype "passive"))
      (node (ref "C2") (pin "1") (pinfunction "1_1") (pintype "passive"))
      (node (ref "C3") (pin "1") (pinfunction "1_1") (pintype "passive"))
      (node (ref "C4") (pin "1") (pinfunction "1_1") (pintype "passive"))
      (node (ref "C5") (pin "1") (pinfunction "1_1") (pintype "passive"))
      (node (ref "C6") (pin "1") (pinfunction "1_1") (pintype "passive"))
      (node (ref "C7") (pin "1") (pinfunction "1_1") (pintype "passive"))
      (node (ref "C8") (pin "1") (pinfunction "1_1") (pintype "passive"))
      (node (ref "C9") (pin "1") (pinfunction "1_1") (pintype "passive"))
      (node (ref "D1") (pin "2") (pinfunction "2_2") (pintype "passive"))
      (node (ref "D2") (pin "2") (pinfunction "2_2") (pintype "passive"))
      (node (ref "D3") (pin "2") (pinfunction "2_2") (pintype "passive"))
      (node (ref "D4") (pin "2") (pinfunction "2_2") (pintype "passive"))
      (node (ref "D5") (pin "2") (pinfunction "2_2") (pintype "passive"))
      (node (ref "D6") (pin "2") (pinfunction "2_2") (pintype "passive"))
      (node (ref "J1") (pin "A1B12") (pinfunction "GND_A1B12_A1B12") (pintype "passive"))
      (node (ref "J1") (pin "B1A12") (pinfunction "GND_B1A12_B1A12") (pintype "passive"))
      (node (ref "J1") (pin "S1") (pinfunction "SHIELD_1_S1") (pintype "passive"))
      (node (ref "J1") (pin "S2") (pinfunction "SHIELD_2_S2") (pintype "passive"))
      (node (ref "J1") (pin "S3") (pinfunction "SHIELD_3_S3") (pintype "passive"))
      (node (ref "J1") (pin "S4") (pinfunction "SHIELD_4_S4") (pintype "passive"))
      (node (ref "J2") (pin "1") (pinfunction "1_1") (pintype "passive"))
      (node (ref "J2") (pin "23") (pinfunction "23_23") (pintype "passive"))
      (node (ref "J3") (pin "2") (pinfunction "2_2") (pintype "passive"))
      (node (ref "J3") (pin "24") (pinfunction "24_24") (pintype "passive"))
      (node (ref "J4") (pin "A1B12") (pinfunction "GND_A1B12_A1B12") (pintype "passive"))
      (node (ref "J4") (pin "B1A12") (pinfunction "GND_B1A12_B1A12") (pintype "passive"))
      (node (ref "J4") (pin "S1") (pinfunction "SHIELD_1_S1") (pintype "passive"))
      (node (ref "J4") (pin "S2") (pinfunction "SHIELD_2_S2") (pintype "passive"))
      (node (ref "J4") (pin "S3") (pinfunction "SHIELD_3_S3") (pintype "passive"))
      (node (ref "J4") (pin "S4") (pinfunction "SHIELD_4_S4") (pintype "passive"))
      (node (ref "LED2") (pin "1") (pinfunction "K_1") (pintype "passive"))
      (node (ref "R10") (pin "1") (pinfunction "1_1") (pintype "passive"))
      (node (ref "R11") (pin "1") (pinfunction "1_1") (pintype "passive"))
      (node (ref "R16") (pin "1") (pinfunction "1_1") (pintype "passive"))
      (node (ref "R17") (pin "1") (pinfunction "1_1") (pintype "passive"))
      (node (ref "R7") (pin "1") (pinfunction "1_1") (pintype "passive"))
      (node (ref "R9") (pin "1") (pinfunction "1_1") (pintype "passive"))
      (node (ref "SW1") (pin "3") (pinfunction "3_3") (pintype "passive"))
      (node (ref "SW1") (pin "4") (pinfunction "4_4") (pintype "passive"))
      (node (ref "SW2") (pin "3") (pinfunction "3_3") (pintype "passive"))
      (node (ref "SW2") (pin "4") (pinfunction "4_4") (pintype "passive"))
      (node (ref "U1") (pin "13") (pinfunction "GND_13") (pintype "passive"))
      (node (ref "U1") (pin "21") (pinfunction "GND_21") (pintype "passive"))
      (node (ref "U1") (pin "3") (pinfunction "GND_3") (pintype "passive"))
      (node (ref "U2") (pin "1") (pinfunction "GND_01_1") (pintype "passive"))
      (node (ref "U2") (pin "2") (pinfunction "GND_02_2") (pintype "passive"))
      (node (ref "U2") (pin "42") (pinfunction "GND_42") (pintype "passive"))
      (node (ref "U2") (pin "43") (pinfunction "GND_43") (pintype "passive"))
      (node (ref "U2") (pin "46") (pinfunction "GND_46_46") (pintype "passive"))
      (node (ref "U2") (pin "47") (pinfunction "GND_47_47") (pintype "passive"))
      (node (ref "U2") (pin "48") (pinfunction "GND_48_48") (pintype "passive"))
      (node (ref "U2") (pin "49") (pinfunction "GND_49_49") (pintype "passive"))
      (node (ref "U2") (pin "50") (pinfunction "GND_50_50") (pintype "passive"))
      (node (ref "U2") (pin "51") (pinfunction "GND_51_51") (pintype "passive"))
      (node (ref "U2") (pin "52") (pinfunction "GND_52_52") (pintype "passive"))
      (node (ref "U2") (pin "53") (pinfunction "GND_53_53") (pintype "passive"))
      (node (ref "U2") (pin "54") (pinfunction "GND_54_54") (pintype "passive"))
      (node (ref "U2") (pin "55") (pinfunction "GND_55_55") (pintype "passive"))
      (node (ref "U2") (pin "56") (pinfunction "GND_56_56") (pintype "passive"))
      (node (ref "U2") (pin "57") (pinfunction "GND_57_57") (pintype "passive"))
      (node (ref "U2") (pin "58") (pinfunction "GND_58_58") (pintype "passive"))
      (node (ref "U2") (pin "59") (pinfunction "GND_59_59") (pintype "passive"))
      (node (ref "U2") (pin "60") (pinfunction "GND_60_60") (pintype "passive"))
      (node (ref "U2") (pin "61") (pinfunction "GND_61_61") (pintype "passive"))
      (node (ref "U2") (pin "62") (pinfunction "GND_62_62") (pintype "passive"))
      (node (ref "U2") (pin "63") (pinfunction "GND_63_63") (pintype "passive"))
      (node (ref "U2") (pin "64") (pinfunction "GND_64_64") (pintype "passive"))
      (node (ref "U2") (pin "65") (pinfunction "GND_65_65") (pintype "passive"))
      (node (ref "U2") (pin "66") (pinfunction "GND_66_66") (pintype "passive"))
      (node (ref "U2") (pin "67") (pinfunction "GND_67_67") (pintype "passive"))
      (node (ref "U2") (pin "68") (pinfunction "GND_68_68") (pintype "passive"))
      (node (ref "U2") (pin "69") (pinfunction "GND_69_69") (pintype "passive"))
      (node (ref "U2") (pin "70") (pinfunction "GND_70_70") (pintype "passive"))
      (node (ref "U2") (pin "71") (pinfunction "GND_71_71") (pintype "passive"))
      (node (ref "U2") (pin "72") (pinfunction "GND_72_72") (pintype "passive"))
      (node (ref "U2") (pin "73") (pinfunction "GND_73_73") (pintype "passive"))
      (node (ref "U3") (pin "2") (pinfunction "GND_2") (pintype "passive"))
      (node (ref "U3") (pin "4") (pinfunction "GND_4") (pintype "passive"))
    )
    (net (code "65") (name "Net-(J1-CC1)") (class "Default")
      (node (ref "J1") (pin "A5") (pinfunction "CC1_A5") (pintype "passive"))
      (node (ref "R10") (pin "2") (pinfunction "2_2") (pintype "passive"))
    )
    (net (code "66") (name "Net-(J1-CC2)") (class "Default")
      (node (ref "J1") (pin "B5") (pinfunction "CC2_B5") (pintype "passive"))
      (node (ref "R9") (pin "2") (pinfunction "2_2") (pintype "passive"))
    )
    (net (code "67") (name "Net-(J4-CC1)") (class "Default")
      (node (ref "J4") (pin "A5") (pinfunction "CC1_A5") (pintype "passive"))
      (node (ref "R17") (pin "2") (pinfunction "2_2") (pintype "passive"))
    )
    (net (code "68") (name "Net-(J4-CC2)") (class "Default")
      (node (ref "J4") (pin "B5") (pinfunction "CC2_B5") (pintype "passive"))
      (node (ref "R16") (pin "2") (pinfunction "2_2") (pintype "passive"))
    )
    (net (code "69") (name "Net-(LED1-+)") (class "Default")
      (node (ref "LED1") (pin "2") (pinfunction "+_2") (pintype "passive"))
      (node (ref "R24") (pin "1") (pinfunction "1_1") (pintype "passive"))
    )
    (net (code "70") (name "Net-(LED2-A)") (class "Default")
      (node (ref "LED2") (pin "2") (pinfunction "A_2") (pintype "passive"))
      (node (ref "R23") (pin "1") (pinfunction "1_1") (pintype "passive"))
    )
    (net (code "71") (name "Net-(Q1-B)") (class "Default")
      (node (ref "Q1") (pin "1") (pinfunction "B_1") (pintype "passive"))
      (node (ref "R25") (pin "1") (pinfunction "1_1") (pintype "passive"))
    )
    (net (code "72") (name "Net-(Q2-B)") (class "Default")
      (node (ref "Q2") (pin "1") (pinfunction "B_1") (pintype "passive"))
      (node (ref "R26") (pin "1") (pinfunction "1_1") (pintype "passive"))
    )
    (net (code "73") (name "Net-(U1-CBUS0)") (class "Default")
      (node (ref "R7") (pin "2") (pinfunction "2_2") (pintype "passive"))
      (node (ref "U1") (pin "15") (pinfunction "CBUS0_15") (pintype "passive"))
    )
    (net (code "74") (name "unconnected-(J1-SBU1-PadA8)") (class "Default")
      (node (ref "J1") (pin "A8") (pinfunction "SBU1_A8") (pintype "passive+no_connect"))
    )
    (net (code "75") (name "unconnected-(J1-SBU2-PadB8)") (class "Default")
      (node (ref "J1") (pin "B8") (pinfunction "SBU2_B8") (pintype "passive+no_connect"))
    )
    (net (code "76") (name "unconnected-(J2-Pad24)") (class "Default")
      (node (ref "J2") (pin "24") (pinfunction "24_24") (pintype "passive+no_connect"))
    )
    (net (code "77") (name "unconnected-(J4-SBU1-PadA8)") (class "Default")
      (node (ref "J4") (pin "A8") (pinfunction "SBU1_A8") (pintype "passive+no_connect"))
    )
    (net (code "78") (name "unconnected-(J4-SBU2-PadB8)") (class "Default")
      (node (ref "J4") (pin "B8") (pinfunction "SBU2_B8") (pintype "passive+no_connect"))
    )
    (net (code "79") (name "unconnected-(U1-CBUS1-Pad14)") (class "Default")
      (node (ref "U1") (pin "14") (pinfunction "CBUS1_14") (pintype "passive+no_connect"))
    )
    (net (code "80") (name "unconnected-(U1-CBUS2-Pad7)") (class "Default")
      (node (ref "U1") (pin "7") (pinfunction "CBUS2_7") (pintype "passive+no_connect"))
    )
    (net (code "81") (name "unconnected-(U1-CTS-Pad6)") (class "Default")
      (node (ref "U1") (pin "6") (pinfunction "CTS_6") (pintype "passive+no_connect"))
    )
    (net (code "82") (name "unconnected-(U1-DCD-Pad5)") (class "Default")
      (node (ref "U1") (pin "5") (pinfunction "DCD_5") (pintype "passive+no_connect"))
    )
    (net (code "83") (name "unconnected-(U1-DSR-Pad4)") (class "Default")
      (node (ref "U1") (pin "4") (pinfunction "DSR_4") (pintype "passive+no_connect"))
    )
    (net (code "84") (name "unconnected-(U1-RI-Pad2)") (class "Default")
      (node (ref "U1") (pin "2") (pinfunction "RI_2") (pintype "passive+no_connect"))
    )
    (net (code "85") (name "unconnected-(U3-OUT-Pad3)") (class "Default")
      (node (ref "U3") (pin "3") (pinfunction "OUT_3") (pintype "passive"))
    )
  )
)
